# Chime_PCB_v2_7_I2C_Counter.net
KiCad netlist of a schematic drawn in EAGLE
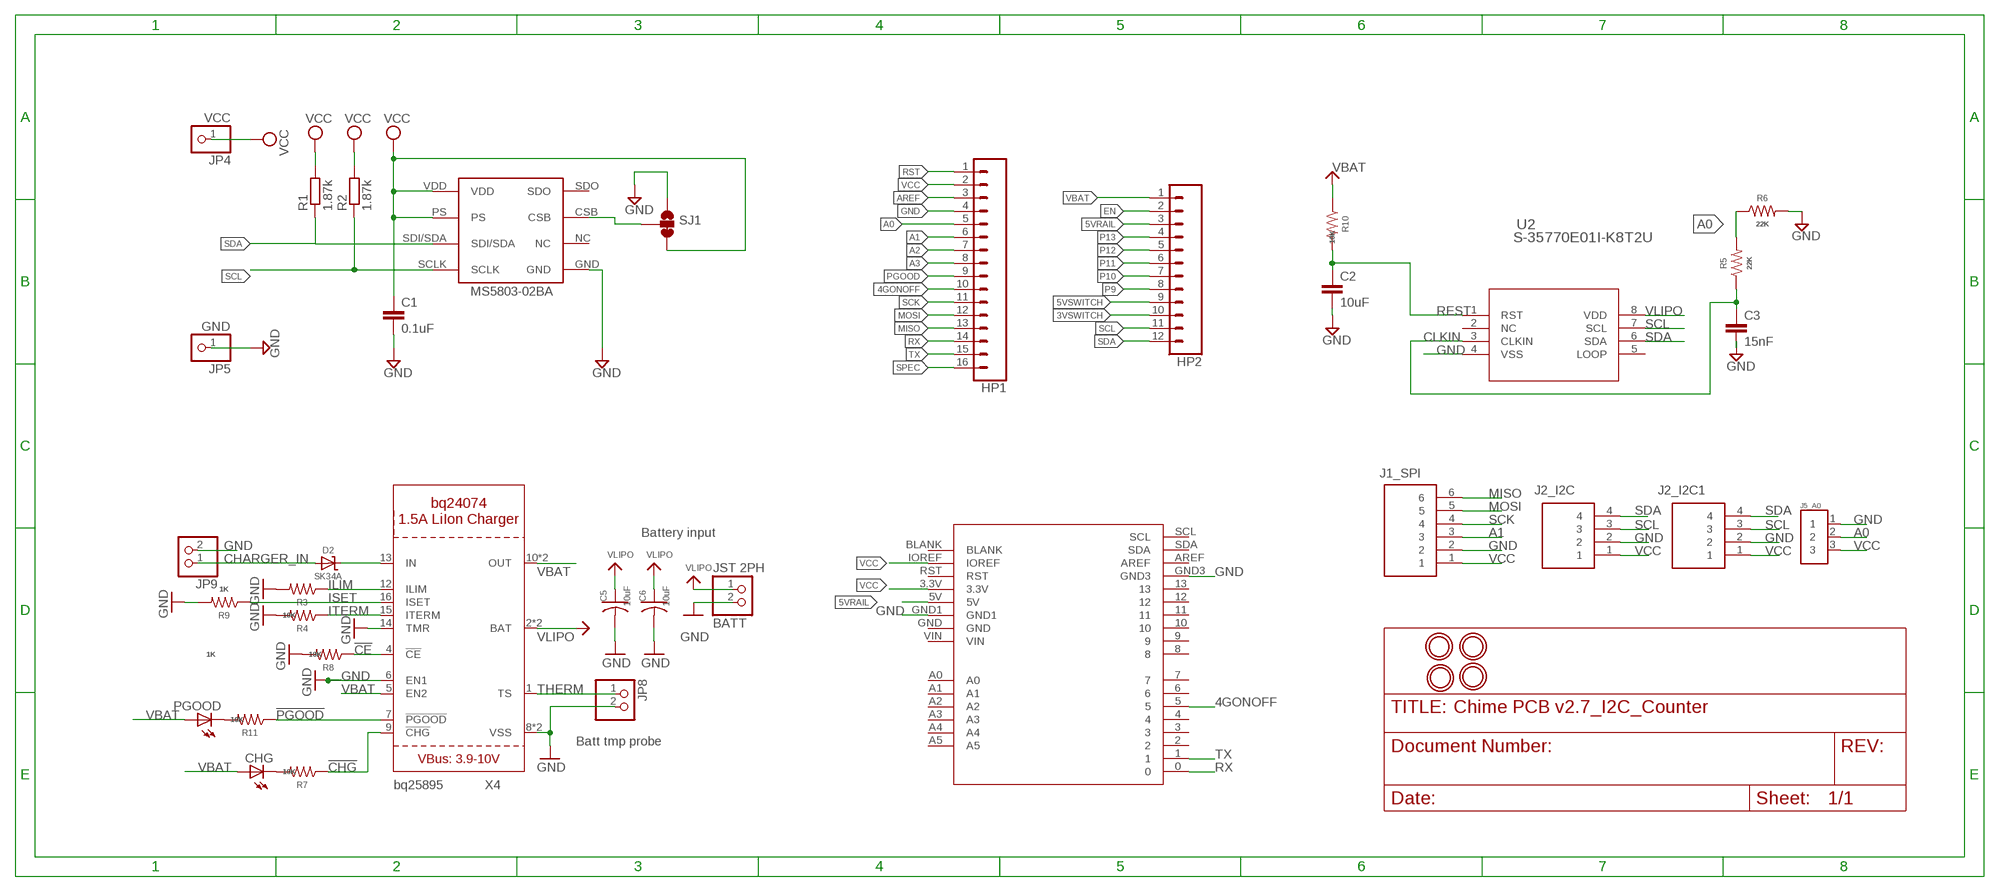
[diagram p0: schematic, sheet 1]

(export (version "E")
  (design (tool "Eeschema 10.0.6"))
  (components
    (comp (ref "BATT")
      (value "JST 2PH")
      (footprint "eagle-import:JST-PH-2-SMT-RA")
      (libsource (lib "eagle-import") (part "JST_2PIN-SMT-RA"))
    )
    (comp (ref "C1")
      (value "0.1uF")
      (footprint "eagle-import:C0805")
      (libsource (lib "eagle-import") (part "C-EUC0805"))
    )
    (comp (ref "C2")
      (value "10uF")
      (footprint "eagle-import:C0805")
      (libsource (lib "eagle-import") (part "C-EUC0805"))
    )
    (comp (ref "C3")
      (value "15nF")
      (footprint "eagle-import:C0805")
      (libsource (lib "eagle-import") (part "C-EUC0805"))
    )
    (comp (ref "C5")
      (value "10uF")
      (footprint "eagle-import:C0805K")
      (libsource (lib "eagle-import") (part "C-USC0805K"))
    )
    (comp (ref "C6")
      (value "10uF")
      (footprint "eagle-import:C0805K")
      (libsource (lib "eagle-import") (part "C-USC0805K"))
    )
    (comp (ref "CHG")
      (value "LEDCHIPLED_0805")
      (footprint "eagle-import:CHIPLED_0805")
      (libsource (lib "eagle-import") (part "LEDCHIPLED_0805"))
    )
    (comp (ref "D2")
      (value "SK34A")
      (footprint "eagle-import:SMADIODE")
      (libsource (lib "eagle-import") (part "DIODE-SCHOTTKYSMA"))
    )
    (comp (ref "HP1")
      (value "CONN_16")
      (footprint "eagle-import:1X16")
      (libsource (lib "eagle-import") (part "CONN_16"))
    )
    (comp (ref "HP2")
      (value "CONN_12")
      (footprint "eagle-import:1X12")
      (libsource (lib "eagle-import") (part "CONN_12"))
    )
    (comp (ref "J1_SPI")
      (value "1725698")
      (footprint "eagle-import:1725698")
      (fields (field (name "MOUSER_PART_NUMBER") "651-1725698"))
      (libsource (lib "eagle-import") (part "1725698"))
    )
    (comp (ref "J2_I2C")
      (value "1725672")
      (footprint "eagle-import:1725672")
      (fields (field (name "MOUSER_PART_NUMBER") "651-1725672"))
      (libsource (lib "eagle-import") (part "1725672"))
    )
    (comp (ref "J2_I2C1")
      (value "1725672")
      (footprint "eagle-import:1725672")
      (fields (field (name "MOUSER_PART_NUMBER") "651-1725672"))
      (libsource (lib "eagle-import") (part "1725672"))
    )
    (comp (ref "J5_A0")
      (value "282834-3")
      (footprint "eagle-import:TE_282834-3")
      (fields (field (name "MF") "TE Connectivity"))
      (libsource (lib "eagle-import") (part "282834-3"))
    )
    (comp (ref "JP4")
      (value "VCC")
      (footprint "eagle-import:1X01")
      (libsource (lib "eagle-import") (part "PINHD-1X1"))
    )
    (comp (ref "JP5")
      (value "GND")
      (footprint "eagle-import:1X01")
      (libsource (lib "eagle-import") (part "PINHD-1X1"))
    )
    (comp (ref "JP8")
      (value "PINHD-1X2")
      (footprint "eagle-import:1X02")
      (libsource (lib "eagle-import") (part "PINHD-1X2"))
    )
    (comp (ref "JP9")
      (value "PINHD-1X2")
      (footprint "eagle-import:1X02")
      (libsource (lib "eagle-import") (part "PINHD-1X2"))
    )
    (comp (ref "PGOOD")
      (value "PGOOD")
      (footprint "eagle-import:CHIPLED_0805")
      (libsource (lib "eagle-import") (part "LEDCHIPLED_0805"))
    )
    (comp (ref "R1")
      (value "1.87k")
      (footprint "eagle-import:R0805")
      (libsource (lib "eagle-import") (part "R-EU_R0805"))
    )
    (comp (ref "R2")
      (value "1.87k")
      (footprint "eagle-import:R0805")
      (libsource (lib "eagle-import") (part "R-EU_R0805"))
    )
    (comp (ref "R3")
      (value "1K")
      (footprint "eagle-import:M0805")
      (libsource (lib "eagle-import") (part "R-US_M0805"))
    )
    (comp (ref "R4")
      (value "10K")
      (footprint "eagle-import:M0805")
      (libsource (lib "eagle-import") (part "R-US_M0805"))
    )
    (comp (ref "R5")
      (value "22K")
      (footprint "eagle-import:M0805")
      (libsource (lib "eagle-import") (part "R-US_M0805"))
    )
    (comp (ref "R6")
      (value "22K")
      (footprint "eagle-import:M0805")
      (libsource (lib "eagle-import") (part "R-US_M0805"))
    )
    (comp (ref "R7")
      (value "10K")
      (footprint "eagle-import:M0805")
      (libsource (lib "eagle-import") (part "R-US_M0805"))
    )
    (comp (ref "R8")
      (value "10K")
      (footprint "eagle-import:M0805")
      (libsource (lib "eagle-import") (part "R-US_M0805"))
    )
    (comp (ref "R9")
      (value "1K")
      (footprint "eagle-import:M0805")
      (libsource (lib "eagle-import") (part "R-US_M0805"))
    )
    (comp (ref "R10")
      (value "10K")
      (footprint "eagle-import:M0805")
      (libsource (lib "eagle-import") (part "R-US_M0805"))
    )
    (comp (ref "R11")
      (value "10K")
      (footprint "eagle-import:M0805")
      (libsource (lib "eagle-import") (part "R-US_M0805"))
    )
    (comp (ref "SJ1")
      (value "JUMPER-SMT_3_1-NC_TRACE_SILK")
      (footprint "eagle-import:SMT-JUMPER_3_1-NC_TRACE_SILK")
      (libsource (lib "eagle-import") (part "JUMPER-SMT_3_1-NC_TRACE_SILK"))
    )
    (comp (ref "U$1")
      (value "LTE_BOARD")
      (footprint "eagle-import:LTE_BOARD_FOOTPRINT")
      (libsource (lib "eagle-import") (part "LTE_BOARD"))
    )
    (comp (ref "U$2")
      (value "MOUNTINGHOLE2.5")
      (footprint "eagle-import:MOUNTINGHOLE_2.5_PLATED")
      (libsource (lib "eagle-import") (part "MOUNTINGHOLE2.5"))
    )
    (comp (ref "U$3")
      (value "MOUNTINGHOLE2.5")
      (footprint "eagle-import:MOUNTINGHOLE_2.5_PLATED")
      (libsource (lib "eagle-import") (part "MOUNTINGHOLE2.5"))
    )
    (comp (ref "U$4")
      (value "MOUNTINGHOLE2.5")
      (footprint "eagle-import:MOUNTINGHOLE_2.5_PLATED")
      (libsource (lib "eagle-import") (part "MOUNTINGHOLE2.5"))
    )
    (comp (ref "U$5")
      (value "MOUNTINGHOLE2.5")
      (footprint "eagle-import:MOUNTINGHOLE_2.5_PLATED")
      (libsource (lib "eagle-import") (part "MOUNTINGHOLE2.5"))
    )
    (comp (ref "U1")
      (value "MS5803-02BA")
      (footprint "eagle-import:MS5803-02BA")
      (libsource (lib "eagle-import") (part "MS5803-02BA"))
    )
    (comp (ref "U2")
      (value "S-35770E01I-K8T2U")
      (footprint "eagle-import:TMSOP08_2P9X2P8_ABL")
      (fields (field (name "COPYRIGHT") "Copyright (C) 2023 Ultra Librarian. All rights reserved."))
      (libsource (lib "eagle-import") (part "S-35770E01I-K8T2U"))
    )
    (comp (ref "X4")
      (value "BQ24074")
      (footprint "eagle-import:QFN16_3MM")
      (libsource (lib "eagle-import") (part "BQ24074"))
    )
  )
  (nets
    (net (code "1") (name "/CHARGER_IN") (class "Default")
      (node (ref "D2") (pin "A") (pinfunction "A_A") (pintype "passive"))
      (node (ref "JP9") (pin "1") (pinfunction "1_1") (pintype "passive"))
    )
    (net (code "2") (name "/CLKIN") (class "Default")
      (node (ref "C3") (pin "1") (pinfunction "1_1") (pintype "passive"))
      (node (ref "R5") (pin "1") (pinfunction "1_1") (pintype "passive"))
      (node (ref "U2") (pin "3") (pinfunction "CLKIN_3") (pintype "passive"))
    )
    (net (code "3") (name "/ILIM") (class "Default")
      (node (ref "R3") (pin "1") (pinfunction "1_1") (pintype "passive"))
      (node (ref "X4") (pin "12") (pinfunction "ILIM_12") (pintype "input"))
    )
    (net (code "4") (name "/ISET") (class "Default")
      (node (ref "R9") (pin "1") (pinfunction "1_1") (pintype "passive"))
      (node (ref "X4") (pin "16") (pinfunction "ISET_16") (pintype "input"))
    )
    (net (code "5") (name "/ITERM") (class "Default")
      (node (ref "R4") (pin "1") (pinfunction "1_1") (pintype "passive"))
      (node (ref "X4") (pin "15") (pinfunction "ITERM_15") (pintype "input"))
    )
    (net (code "6") (name "/REST") (class "Default")
      (node (ref "C2") (pin "1") (pinfunction "1_1") (pintype "passive"))
      (node (ref "R10") (pin "2") (pinfunction "2_2") (pintype "passive"))
      (node (ref "U2") (pin "1") (pinfunction "RST_1") (pintype "passive"))
    )
    (net (code "7") (name "/THERM") (class "Default")
      (node (ref "JP8") (pin "1") (pinfunction "1_1") (pintype "passive"))
      (node (ref "X4") (pin "1") (pinfunction "TS_1") (pintype "input"))
    )
    (net (code "8") (name "/~{CE}") (class "Default")
      (node (ref "R8") (pin "1") (pinfunction "1_1") (pintype "passive"))
      (node (ref "X4") (pin "4") (pinfunction "~{CE}_4") (pintype "input"))
    )
    (net (code "9") (name "/~{CHG}") (class "Default")
      (node (ref "R7") (pin "1") (pinfunction "1_1") (pintype "passive"))
      (node (ref "X4") (pin "9") (pinfunction "~{CHG}_9") (pintype "output"))
    )
    (net (code "10") (name "/~{PGOOD}") (class "Default")
      (node (ref "R11") (pin "1") (pinfunction "1_1") (pintype "passive"))
      (node (ref "X4") (pin "7") (pinfunction "~{PGOOD}_7") (pintype "output"))
    )
    (net (code "11") (name "3VSWITCH") (class "Default")
      (node (ref "HP2") (pin "10") (pinfunction "10_10") (pintype "passive"))
    )
    (net (code "12") (name "4GONOFF") (class "Default")
      (node (ref "HP1") (pin "10") (pinfunction "10_10") (pintype "passive"))
      (node (ref "U$1") (pin "5") (pinfunction "5_5") (pintype "bidirectional"))
    )
    (net (code "13") (name "5VRAIL") (class "Default")
      (node (ref "HP2") (pin "3") (pinfunction "3_3") (pintype "passive"))
      (node (ref "U$1") (pin "5V") (pinfunction "5V_5V") (pintype "bidirectional"))
    )
    (net (code "14") (name "5VSWITCH") (class "Default")
      (node (ref "HP2") (pin "9") (pinfunction "9_9") (pintype "passive"))
    )
    (net (code "15") (name "A0") (class "Default")
      (node (ref "HP1") (pin "5") (pinfunction "5_5") (pintype "passive"))
      (node (ref "J5_A0") (pin "2") (pinfunction "2_2") (pintype "passive"))
      (node (ref "R5") (pin "2") (pinfunction "2_2") (pintype "passive"))
      (node (ref "R6") (pin "1") (pinfunction "1_1") (pintype "passive"))
    )
    (net (code "16") (name "A1") (class "Default")
      (node (ref "HP1") (pin "6") (pinfunction "6_6") (pintype "passive"))
      (node (ref "J1_SPI") (pin "3") (pinfunction "3_3") (pintype "bidirectional"))
    )
    (net (code "17") (name "A2") (class "Default")
      (node (ref "HP1") (pin "7") (pinfunction "7_7") (pintype "passive"))
    )
    (net (code "18") (name "A3") (class "Default")
      (node (ref "HP1") (pin "8") (pinfunction "8_8") (pintype "passive"))
    )
    (net (code "19") (name "AREF") (class "Default")
      (node (ref "HP1") (pin "3") (pinfunction "3_3") (pintype "passive"))
    )
    (net (code "20") (name "EN") (class "Default")
      (node (ref "HP2") (pin "2") (pinfunction "2_2") (pintype "passive"))
    )
    (net (code "21") (name "GND") (class "Default")
      (node (ref "BATT") (pin "2") (pinfunction "1_2") (pintype "passive"))
      (node (ref "C1") (pin "2") (pinfunction "2_2") (pintype "passive"))
      (node (ref "C2") (pin "2") (pinfunction "2_2") (pintype "passive"))
      (node (ref "C3") (pin "2") (pinfunction "2_2") (pintype "passive"))
      (node (ref "C5") (pin "2") (pinfunction "2_2") (pintype "passive"))
      (node (ref "C6") (pin "2") (pinfunction "2_2") (pintype "passive"))
      (node (ref "HP1") (pin "4") (pinfunction "4_4") (pintype "passive"))
      (node (ref "J1_SPI") (pin "2") (pinfunction "2_2") (pintype "bidirectional"))
      (node (ref "J2_I2C") (pin "2") (pinfunction "2_2") (pintype "bidirectional"))
      (node (ref "J2_I2C1") (pin "2") (pinfunction "2_2") (pintype "bidirectional"))
      (node (ref "J5_A0") (pin "1") (pinfunction "1_1") (pintype "passive"))
      (node (ref "JP5") (pin "1") (pinfunction "1_1") (pintype "passive"))
      (node (ref "JP8") (pin "2") (pinfunction "2_2") (pintype "passive"))
      (node (ref "JP9") (pin "2") (pinfunction "2_2") (pintype "passive"))
      (node (ref "R3") (pin "2") (pinfunction "2_2") (pintype "passive"))
      (node (ref "R4") (pin "2") (pinfunction "2_2") (pintype "passive"))
      (node (ref "R6") (pin "2") (pinfunction "2_2") (pintype "passive"))
      (node (ref "R8") (pin "2") (pinfunction "2_2") (pintype "passive"))
      (node (ref "R9") (pin "2") (pinfunction "2_2") (pintype "passive"))
      (node (ref "SJ1") (pin "1") (pinfunction "1_1") (pintype "passive"))
      (node (ref "U$1") (pin "GND1") (pinfunction "GND1_GND1") (pintype "bidirectional"))
      (node (ref "U$1") (pin "GND3") (pinfunction "GND3_GND3") (pintype "bidirectional"))
      (node (ref "U1") (pin "GND") (pinfunction "GND_GND") (pintype "bidirectional"))
      (node (ref "U2") (pin "4") (pinfunction "VSS_4") (pintype "passive"))
      (node (ref "X4") (pin "14") (pinfunction "TMR_14") (pintype "input"))
      (node (ref "X4") (pin "6") (pinfunction "EN1_6") (pintype "input"))
      (node (ref "X4") (pin "8") (pinfunction "VSS_8") (pintype "power_in"))
      (node (ref "X4") (pin "THERMAL") (pinfunction "VSS_THERMAL") (pintype "power_in"))
    )
    (net (code "22") (name "MISO") (class "Default")
      (node (ref "HP1") (pin "13") (pinfunction "13_13") (pintype "passive"))
      (node (ref "J1_SPI") (pin "6") (pinfunction "6_6") (pintype "bidirectional"))
    )
    (net (code "23") (name "MOSI") (class "Default")
      (node (ref "HP1") (pin "12") (pinfunction "12_12") (pintype "passive"))
      (node (ref "J1_SPI") (pin "5") (pinfunction "5_5") (pintype "bidirectional"))
    )
    (net (code "24") (name "Net-(CHG-PadC)") (class "Default")
      (node (ref "CHG") (pin "C") (pinfunction "C_C") (pintype "passive"))
      (node (ref "R7") (pin "2") (pinfunction "2_2") (pintype "passive"))
    )
    (net (code "25") (name "Net-(PGOOD-PadC)") (class "Default")
      (node (ref "PGOOD") (pin "C") (pinfunction "C_C") (pintype "passive"))
      (node (ref "R11") (pin "2") (pinfunction "2_2") (pintype "passive"))
    )
    (net (code "26") (name "Net-(SJ1-Pad2)") (class "Default")
      (node (ref "SJ1") (pin "2") (pinfunction "2_2") (pintype "passive"))
      (node (ref "U1") (pin "CSB") (pinfunction "CSB_CSB") (pintype "bidirectional"))
    )
    (net (code "27") (name "Net-(X4-IN)") (class "Default")
      (node (ref "D2") (pin "C") (pinfunction "C_C") (pintype "passive"))
      (node (ref "X4") (pin "13") (pinfunction "IN_13") (pintype "power_in"))
    )
    (net (code "28") (name "P9") (class "Default")
      (node (ref "HP2") (pin "8") (pinfunction "8_8") (pintype "passive"))
    )
    (net (code "29") (name "P10") (class "Default")
      (node (ref "HP2") (pin "7") (pinfunction "7_7") (pintype "passive"))
    )
    (net (code "30") (name "P11") (class "Default")
      (node (ref "HP2") (pin "6") (pinfunction "6_6") (pintype "passive"))
    )
    (net (code "31") (name "P12") (class "Default")
      (node (ref "HP2") (pin "5") (pinfunction "5_5") (pintype "passive"))
    )
    (net (code "32") (name "P13") (class "Default")
      (node (ref "HP2") (pin "4") (pinfunction "4_4") (pintype "passive"))
    )
    (net (code "33") (name "PGOOD") (class "Default")
      (node (ref "HP1") (pin "9") (pinfunction "9_9") (pintype "passive"))
    )
    (net (code "34") (name "RST") (class "Default")
      (node (ref "HP1") (pin "1") (pinfunction "1_1") (pintype "passive"))
    )
    (net (code "35") (name "RX") (class "Default")
      (node (ref "HP1") (pin "14") (pinfunction "14_14") (pintype "passive"))
      (node (ref "U$1") (pin "0") (pinfunction "0_0") (pintype "bidirectional"))
    )
    (net (code "36") (name "SCK") (class "Default")
      (node (ref "HP1") (pin "11") (pinfunction "11_11") (pintype "passive"))
      (node (ref "J1_SPI") (pin "4") (pinfunction "4_4") (pintype "bidirectional"))
    )
    (net (code "37") (name "SCL") (class "Default")
      (node (ref "HP2") (pin "11") (pinfunction "11_11") (pintype "passive"))
      (node (ref "J2_I2C") (pin "3") (pinfunction "3_3") (pintype "bidirectional"))
      (node (ref "J2_I2C1") (pin "3") (pinfunction "3_3") (pintype "bidirectional"))
      (node (ref "R2") (pin "1") (pinfunction "1_1") (pintype "passive"))
      (node (ref "U1") (pin "SCLK") (pinfunction "SCLK_SCLK") (pintype "bidirectional"))
      (node (ref "U2") (pin "7") (pinfunction "SCL_7") (pintype "passive"))
    )
    (net (code "38") (name "SDA") (class "Default")
      (node (ref "HP2") (pin "12") (pinfunction "12_12") (pintype "passive"))
      (node (ref "J2_I2C") (pin "4") (pinfunction "4_4") (pintype "bidirectional"))
      (node (ref "J2_I2C1") (pin "4") (pinfunction "4_4") (pintype "bidirectional"))
      (node (ref "R1") (pin "1") (pinfunction "1_1") (pintype "passive"))
      (node (ref "U1") (pin "SDI/SDA") (pinfunction "SDI/SDA_SDI/SDA") (pintype "bidirectional"))
      (node (ref "U2") (pin "6") (pinfunction "SDA_6") (pintype "passive"))
    )
    (net (code "39") (name "SPEC") (class "Default")
      (node (ref "HP1") (pin "16") (pinfunction "16_16") (pintype "passive"))
    )
    (net (code "40") (name "TX") (class "Default")
      (node (ref "HP1") (pin "15") (pinfunction "15_15") (pintype "passive"))
      (node (ref "U$1") (pin "1") (pinfunction "1_1") (pintype "bidirectional"))
    )
    (net (code "41") (name "VBAT") (class "Default")
      (node (ref "CHG") (pin "A") (pinfunction "A_A") (pintype "passive"))
      (node (ref "HP2") (pin "1") (pinfunction "1_1") (pintype "passive"))
      (node (ref "PGOOD") (pin "A") (pinfunction "A_A") (pintype "passive"))
      (node (ref "R10") (pin "1") (pinfunction "1_1") (pintype "passive"))
      (node (ref "X4") (pin "10") (pinfunction "OUT_10") (pintype "output"))
      (node (ref "X4") (pin "11") (pinfunction "OUT_11") (pintype "output"))
      (node (ref "X4") (pin "5") (pinfunction "EN2_5") (pintype "input"))
    )
    (net (code "42") (name "VCC") (class "Default")
      (node (ref "C1") (pin "1") (pinfunction "1_1") (pintype "passive"))
      (node (ref "HP1") (pin "2") (pinfunction "2_2") (pintype "passive"))
      (node (ref "J1_SPI") (pin "1") (pinfunction "1_1") (pintype "bidirectional"))
      (node (ref "J2_I2C") (pin "1") (pinfunction "1_1") (pintype "bidirectional"))
      (node (ref "J2_I2C1") (pin "1") (pinfunction "1_1") (pintype "bidirectional"))
      (node (ref "J5_A0") (pin "3") (pinfunction "3_3") (pintype "passive"))
      (node (ref "JP4") (pin "1") (pinfunction "1_1") (pintype "passive"))
      (node (ref "R1") (pin "2") (pinfunction "2_2") (pintype "passive"))
      (node (ref "R2") (pin "2") (pinfunction "2_2") (pintype "passive"))
      (node (ref "SJ1") (pin "3") (pinfunction "3_3") (pintype "passive"))
      (node (ref "U$1") (pin "3.3V") (pinfunction "3.3V_3.3V") (pintype "bidirectional"))
      (node (ref "U$1") (pin "IOREF") (pinfunction "IOREF_IOREF") (pintype "bidirectional"))
      (node (ref "U1") (pin "PS") (pinfunction "PS_PS") (pintype "bidirectional"))
      (node (ref "U1") (pin "VDD") (pinfunction "VDD_VDD") (pintype "bidirectional"))
    )
    (net (code "43") (name "VLIPO") (class "Default")
      (node (ref "BATT") (pin "1") (pinfunction "2_1") (pintype "passive"))
      (node (ref "C5") (pin "1") (pinfunction "1_1") (pintype "passive"))
      (node (ref "C6") (pin "1") (pinfunction "1_1") (pintype "passive"))
      (node (ref "U2") (pin "8") (pinfunction "VDD_8") (pintype "power_in"))
      (node (ref "X4") (pin "2") (pinfunction "BAT_2") (pintype "input"))
      (node (ref "X4") (pin "3") (pinfunction "BAT_3") (pintype "input"))
    )
    (net (code "44") (name "unconnected-(U$1-Pad2)") (class "Default")
      (node (ref "U$1") (pin "2") (pinfunction "2_2") (pintype "bidirectional"))
    )
    (net (code "45") (name "unconnected-(U$1-Pad3)") (class "Default")
      (node (ref "U$1") (pin "3") (pinfunction "3_3") (pintype "bidirectional"))
    )
    (net (code "46") (name "unconnected-(U$1-Pad4)") (class "Default")
      (node (ref "U$1") (pin "4") (pinfunction "4_4") (pintype "bidirectional"))
    )
    (net (code "47") (name "unconnected-(U$1-Pad6)") (class "Default")
      (node (ref "U$1") (pin "6") (pinfunction "6_6") (pintype "bidirectional"))
    )
    (net (code "48") (name "unconnected-(U$1-Pad7)") (class "Default")
      (node (ref "U$1") (pin "7") (pinfunction "7_7") (pintype "bidirectional"))
    )
    (net (code "49") (name "unconnected-(U$1-Pad8)") (class "Default")
      (node (ref "U$1") (pin "8") (pinfunction "8_8") (pintype "bidirectional"))
    )
    (net (code "50") (name "unconnected-(U$1-Pad9)") (class "Default")
      (node (ref "U$1") (pin "9") (pinfunction "9_9") (pintype "bidirectional"))
    )
    (net (code "51") (name "unconnected-(U$1-Pad10)") (class "Default")
      (node (ref "U$1") (pin "10") (pinfunction "10_10") (pintype "bidirectional"))
    )
    (net (code "52") (name "unconnected-(U$1-Pad11)") (class "Default")
      (node (ref "U$1") (pin "11") (pinfunction "11_11") (pintype "bidirectional"))
    )
    (net (code "53") (name "unconnected-(U$1-Pad12)") (class "Default")
      (node (ref "U$1") (pin "12") (pinfunction "12_12") (pintype "bidirectional"))
    )
    (net (code "54") (name "unconnected-(U$1-Pad13)") (class "Default")
      (node (ref "U$1") (pin "13") (pinfunction "13_13") (pintype "bidirectional"))
    )
    (net (code "55") (name "unconnected-(U$1-PadA0)") (class "Default")
      (node (ref "U$1") (pin "A0") (pinfunction "A0_A0") (pintype "bidirectional"))
    )
    (net (code "56") (name "unconnected-(U$1-PadA1)") (class "Default")
      (node (ref "U$1") (pin "A1") (pinfunction "A1_A1") (pintype "bidirectional"))
    )
    (net (code "57") (name "unconnected-(U$1-PadA2)") (class "Default")
      (node (ref "U$1") (pin "A2") (pinfunction "A2_A2") (pintype "bidirectional"))
    )
    (net (code "58") (name "unconnected-(U$1-PadA3)") (class "Default")
      (node (ref "U$1") (pin "A3") (pinfunction "A3_A3") (pintype "bidirectional"))
    )
    (net (code "59") (name "unconnected-(U$1-PadA4)") (class "Default")
      (node (ref "U$1") (pin "A4") (pinfunction "A4_A4") (pintype "bidirectional"))
    )
    (net (code "60") (name "unconnected-(U$1-PadA5)") (class "Default")
      (node (ref "U$1") (pin "A5") (pinfunction "A5_A5") (pintype "bidirectional"))
    )
    (net (code "61") (name "unconnected-(U$1-PadAREF)") (class "Default")
      (node (ref "U$1") (pin "AREF") (pinfunction "AREF_AREF") (pintype "bidirectional"))
    )
    (net (code "62") (name "unconnected-(U$1-PadBLANK)") (class "Default")
      (node (ref "U$1") (pin "BLANK") (pinfunction "BLANK_BLANK") (pintype "bidirectional"))
    )
    (net (code "63") (name "unconnected-(U$1-PadGND)") (class "Default")
      (node (ref "U$1") (pin "GND") (pinfunction "GND_GND") (pintype "bidirectional"))
    )
    (net (code "64") (name "unconnected-(U$1-PadRST)") (class "Default")
      (node (ref "U$1") (pin "RST") (pinfunction "RST_RST") (pintype "bidirectional"))
    )
    (net (code "65") (name "unconnected-(U$1-PadSCL)") (class "Default")
      (node (ref "U$1") (pin "SCL") (pinfunction "SCL_SCL") (pintype "bidirectional"))
    )
    (net (code "66") (name "unconnected-(U$1-PadSDA)") (class "Default")
      (node (ref "U$1") (pin "SDA") (pinfunction "SDA_SDA") (pintype "bidirectional"))
    )
    (net (code "67") (name "unconnected-(U$1-PadVIN)") (class "Default")
      (node (ref "U$1") (pin "VIN") (pinfunction "VIN_VIN") (pintype "bidirectional"))
    )
    (net (code "68") (name "unconnected-(U1-PadNC)") (class "Default")
      (node (ref "U1") (pin "NC") (pinfunction "NC_NC") (pintype "bidirectional"))
    )
    (net (code "69") (name "unconnected-(U1-PadSDO)") (class "Default")
      (node (ref "U1") (pin "SDO") (pinfunction "SDO_SDO") (pintype "bidirectional"))
    )
    (net (code "70") (name "unconnected-(U2-LOOP-Pad5)") (class "Default")
      (node (ref "U2") (pin "5") (pinfunction "LOOP_5") (pintype "passive"))
    )
    (net (code "71") (name "unconnected-(U2-NC-Pad2)") (class "Default")
      (node (ref "U2") (pin "2") (pinfunction "NC_2") (pintype "no_connect"))
    )
  )
)
